# EspejoCorriente.net
KiCad netlist of a schematic drawn in Altium Designer
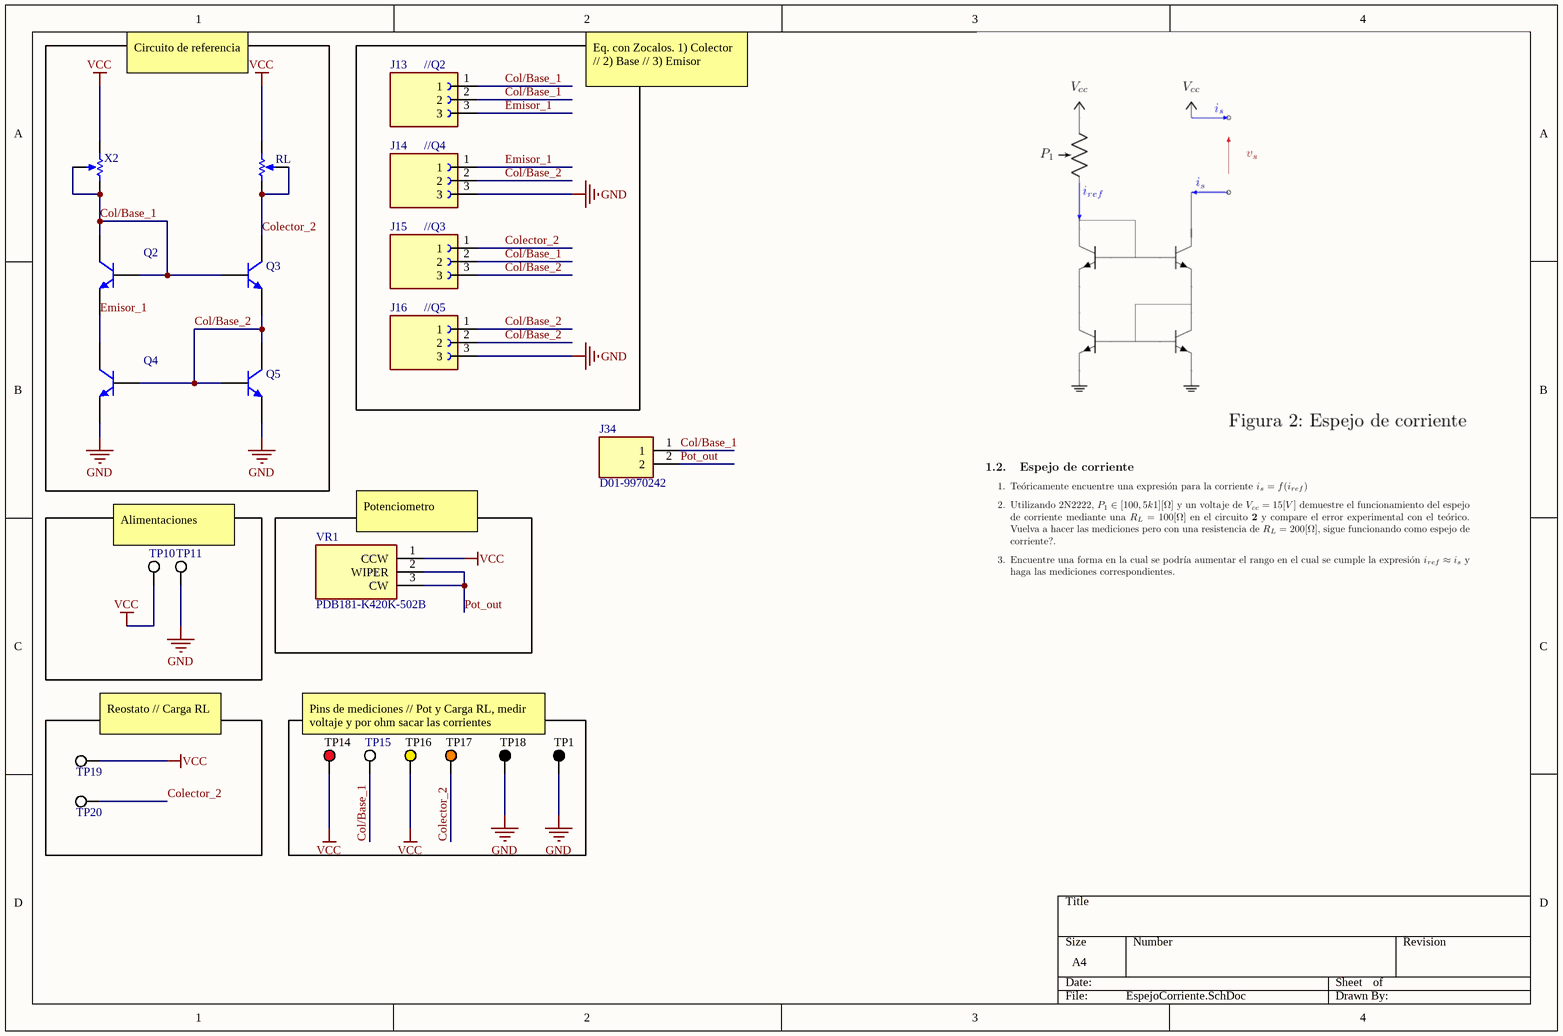
[diagram p0: EspejoCorriente.SchDoc]

(export (version "E")
  (design (tool "Eeschema 10.0.6"))
  (components
    (comp (ref "J13")
      (value "D01-9970342")
      (footprint "HARWIN_D01-9970342")
      (libsource (lib "Zocalo_3pines") (part "D01-9970342"))
    )
    (comp (ref "J14")
      (value "D01-9970342")
      (footprint "HARWIN_D01-9970342")
      (libsource (lib "Zocalo_3pines") (part "D01-9970342"))
    )
    (comp (ref "J15")
      (value "D01-9970342")
      (footprint "HARWIN_D01-9970342")
      (libsource (lib "Zocalo_3pines") (part "D01-9970342"))
    )
    (comp (ref "J16")
      (value "D01-9970342")
      (footprint "HARWIN_D01-9970342")
      (libsource (lib "Zocalo_3pines") (part "D01-9970342"))
    )
    (comp (ref "J34")
      (value "D01-9970242")
      (footprint "D019970242")
      (description "IC Socket: 2 Pos Receptacle SIL Straight THT Strip")
      (fields (field (name "MOUSER PART NUMBER") "855-D01-9970242"))
      (libsource (lib "Zocalo_2pines") (part "D01-9970242"))
    )
    (comp (ref "Q2")
      (value "Bipolar NPN 3 Pins Transistor VBIC Model")
      (libsource (lib "Simulation Generic Components") (part "BJT NPN VBIC"))
    )
    (comp (ref "Q3")
      (value "Bipolar NPN 3 Pins Transistor VBIC Model")
      (libsource (lib "Simulation Generic Components") (part "BJT NPN VBIC"))
    )
    (comp (ref "Q4")
      (value "Bipolar NPN 3 Pins Transistor VBIC Model")
      (libsource (lib "Simulation Generic Components") (part "BJT NPN VBIC"))
    )
    (comp (ref "Q5")
      (value "Bipolar NPN 3 Pins Transistor VBIC Model")
      (libsource (lib "Simulation Generic Components") (part "BJT NPN VBIC"))
    )
    (comp (ref "RL")
      (value "Potentiometer")
      (libsource (lib "Simulation Generic Components") (part "Potentiometer"))
    )
    (comp (ref "TP1")
      (value "5011")
      (footprint "KSTN-5011_V")
      (description "Test Point, Black, Through Hole, RoHS, Bulk")
      (fields (field (name "MANUFACTURER") "Keystone"))
      (libsource (lib "Altium Content Vault") (part "TESTPOINT_BLACK"))
    )
    (comp (ref "TP10")
      (value "575-4")
      (footprint "KSTN-575-4")
      (description "Banana Jack, Non-Insulated, 1-Pin THD, RoHS, Bulk")
      (fields (field (name "MANUFACTURER") "Keystone-Electronics"))
      (libsource (lib "Altium Content Vault") (part "TESTPOINT_WHITE"))
    )
    (comp (ref "TP11")
      (value "575-4")
      (footprint "KSTN-575-4")
      (description "Banana Jack, Non-Insulated, 1-Pin THD, RoHS, Bulk")
      (fields (field (name "MANUFACTURER") "Keystone-Electronics"))
      (libsource (lib "Altium Content Vault") (part "TESTPOINT_WHITE"))
    )
    (comp (ref "TP14")
      (value "5010")
      (footprint "KSTN-5010_V")
      (description "Test Point, Red, Through Hole, RoHS, Bulk")
      (fields (field (name "MANUFACTURER") "Keystone"))
      (libsource (lib "Altium Content Vault") (part "TESTPOINT_RED"))
    )
    (comp (ref "TP15")
      (value "5012")
      (footprint "KSTN-5012_V")
      (description "Test Point, White, Through Hole, RoHS, Bulk")
      (fields (field (name "MANUFACTURER") "Keystone"))
      (libsource (lib "Altium Content Vault") (part "TESTPOINT_WHITE"))
    )
    (comp (ref "TP16")
      (value "5014")
      (footprint "KSTN-5014_V")
      (description "Test Point, Yellow, Through Hole, RoHS, Bulk")
      (fields (field (name "MANUFACTURER") "Keystone"))
      (libsource (lib "Altium Content Vault") (part "TESTPOINT_YELLOW"))
    )
    (comp (ref "TP17")
      (value "5013")
      (footprint "KSTN-5013_V")
      (description "Test Point, Orange, Through Hole, RoHS, Bulk")
      (fields (field (name "MANUFACTURER") "Keystone"))
      (libsource (lib "Altium Content Vault") (part "TESTPOINT_ORANGE"))
    )
    (comp (ref "TP18")
      (value "5011")
      (footprint "KSTN-5011_V")
      (description "Test Point, Black, Through Hole, RoHS, Bulk")
      (fields (field (name "MANUFACTURER") "Keystone"))
      (libsource (lib "Altium Content Vault") (part "TESTPOINT_BLACK"))
    )
    (comp (ref "TP19")
      (value "575-4")
      (footprint "KSTN-575-4")
      (description "Banana Jack, Non-Insulated, 1-Pin THD, RoHS, Bulk")
      (fields (field (name "MANUFACTURER") "Keystone-Electronics"))
      (libsource (lib "Altium Content Vault") (part "TESTPOINT_WHITE"))
    )
    (comp (ref "TP20")
      (value "575-4")
      (footprint "KSTN-575-4")
      (description "Banana Jack, Non-Insulated, 1-Pin THD, RoHS, Bulk")
      (fields (field (name "MANUFACTURER") "Keystone-Electronics"))
      (libsource (lib "Altium Content Vault") (part "TESTPOINT_WHITE"))
    )
    (comp (ref "VR1")
      (value "PDB181-K420K-502B")
      (footprint "Potenciometro5K:PDB181K220K104B")
      (description "Variable Resistor")
      (fields (field (name "MOUSER PART NUMBER") "652-PDB181-K420K502B"))
      (libsource (lib "Potenciometro5K") (part "PDB181-K420K-502B"))
    )
    (comp (ref "X2")
      (value "Potentiometer")
      (libsource (lib "Simulation Generic Components") (part "Potentiometer"))
    )
  )
  (nets
    (net (code "1") (name "/Colector_2") (class "Default")
      (node (ref "J15") (pin "1") (pinfunction "1_1") (pintype "passive"))
      (node (ref "Q3") (pin "1") (pinfunction "C_1") (pintype "passive"))
      (node (ref "RL") (pin "1") (pinfunction "TOP_1") (pintype "passive"))
      (node (ref "RL") (pin "3") (pinfunction "TAP_3") (pintype "passive"))
      (node (ref "TP17") (pin "1") (pinfunction "1_1") (pintype "passive"))
      (node (ref "TP20") (pin "1") (pinfunction "1_1") (pintype "passive"))
    )
    (net (code "2") (name "/Col{slash}Base_1") (class "Default")
      (node (ref "J13") (pin "1") (pinfunction "1_1") (pintype "passive"))
      (node (ref "J13") (pin "2") (pinfunction "2_2") (pintype "passive"))
      (node (ref "J15") (pin "2") (pinfunction "2_2") (pintype "passive"))
      (node (ref "J34") (pin "1") (pinfunction "1_1") (pintype "passive"))
      (node (ref "Q2") (pin "1") (pinfunction "C_1") (pintype "passive"))
      (node (ref "Q2") (pin "2") (pinfunction "B_2") (pintype "passive"))
      (node (ref "Q3") (pin "2") (pinfunction "B_2") (pintype "passive"))
      (node (ref "TP15") (pin "1") (pinfunction "1_1") (pintype "passive"))
      (node (ref "X2") (pin "2") (pinfunction "BOT_2") (pintype "passive"))
      (node (ref "X2") (pin "3") (pinfunction "TAP_3") (pintype "passive"))
    )
    (net (code "3") (name "/Col{slash}Base_2") (class "Default")
      (node (ref "J14") (pin "2") (pinfunction "2_2") (pintype "passive"))
      (node (ref "J15") (pin "3") (pinfunction "3_3") (pintype "passive"))
      (node (ref "J16") (pin "1") (pinfunction "1_1") (pintype "passive"))
      (node (ref "J16") (pin "2") (pinfunction "2_2") (pintype "passive"))
      (node (ref "Q3") (pin "3") (pinfunction "E_3") (pintype "passive"))
      (node (ref "Q4") (pin "2") (pinfunction "B_2") (pintype "passive"))
      (node (ref "Q5") (pin "1") (pinfunction "C_1") (pintype "passive"))
      (node (ref "Q5") (pin "2") (pinfunction "B_2") (pintype "passive"))
    )
    (net (code "4") (name "/Emisor_1") (class "Default")
      (node (ref "J13") (pin "3") (pinfunction "3_3") (pintype "passive"))
      (node (ref "J14") (pin "1") (pinfunction "1_1") (pintype "passive"))
      (node (ref "Q2") (pin "3") (pinfunction "E_3") (pintype "passive"))
      (node (ref "Q4") (pin "1") (pinfunction "C_1") (pintype "passive"))
    )
    (net (code "5") (name "/Pot_out") (class "Default")
      (node (ref "J34") (pin "2") (pinfunction "2_2") (pintype "passive"))
      (node (ref "VR1") (pin "2") (pinfunction "WIPER_2") (pintype "passive"))
      (node (ref "VR1") (pin "3") (pinfunction "CW_3") (pintype "passive"))
    )
    (net (code "6") (name "GND") (class "Default")
      (node (ref "J14") (pin "3") (pinfunction "3_3") (pintype "passive"))
      (node (ref "J16") (pin "3") (pinfunction "3_3") (pintype "passive"))
      (node (ref "Q4") (pin "3") (pinfunction "E_3") (pintype "passive"))
      (node (ref "Q5") (pin "3") (pinfunction "E_3") (pintype "passive"))
      (node (ref "TP1") (pin "1") (pinfunction "1_1") (pintype "passive"))
      (node (ref "TP11") (pin "1") (pinfunction "1_1") (pintype "passive"))
      (node (ref "TP18") (pin "1") (pinfunction "1_1") (pintype "passive"))
    )
    (net (code "7") (name "VCC") (class "Default")
      (node (ref "RL") (pin "2") (pinfunction "BOT_2") (pintype "passive"))
      (node (ref "TP10") (pin "1") (pinfunction "1_1") (pintype "passive"))
      (node (ref "TP14") (pin "1") (pinfunction "1_1") (pintype "passive"))
      (node (ref "TP16") (pin "1") (pinfunction "1_1") (pintype "passive"))
      (node (ref "TP19") (pin "1") (pinfunction "1_1") (pintype "passive"))
      (node (ref "VR1") (pin "1") (pinfunction "CCW_1") (pintype "passive"))
      (node (ref "X2") (pin "1") (pinfunction "TOP_1") (pintype "passive"))
    )
  )
)
